# eCog002_Proto_SMD.net
KiCad netlist of a schematic drawn in EAGLE
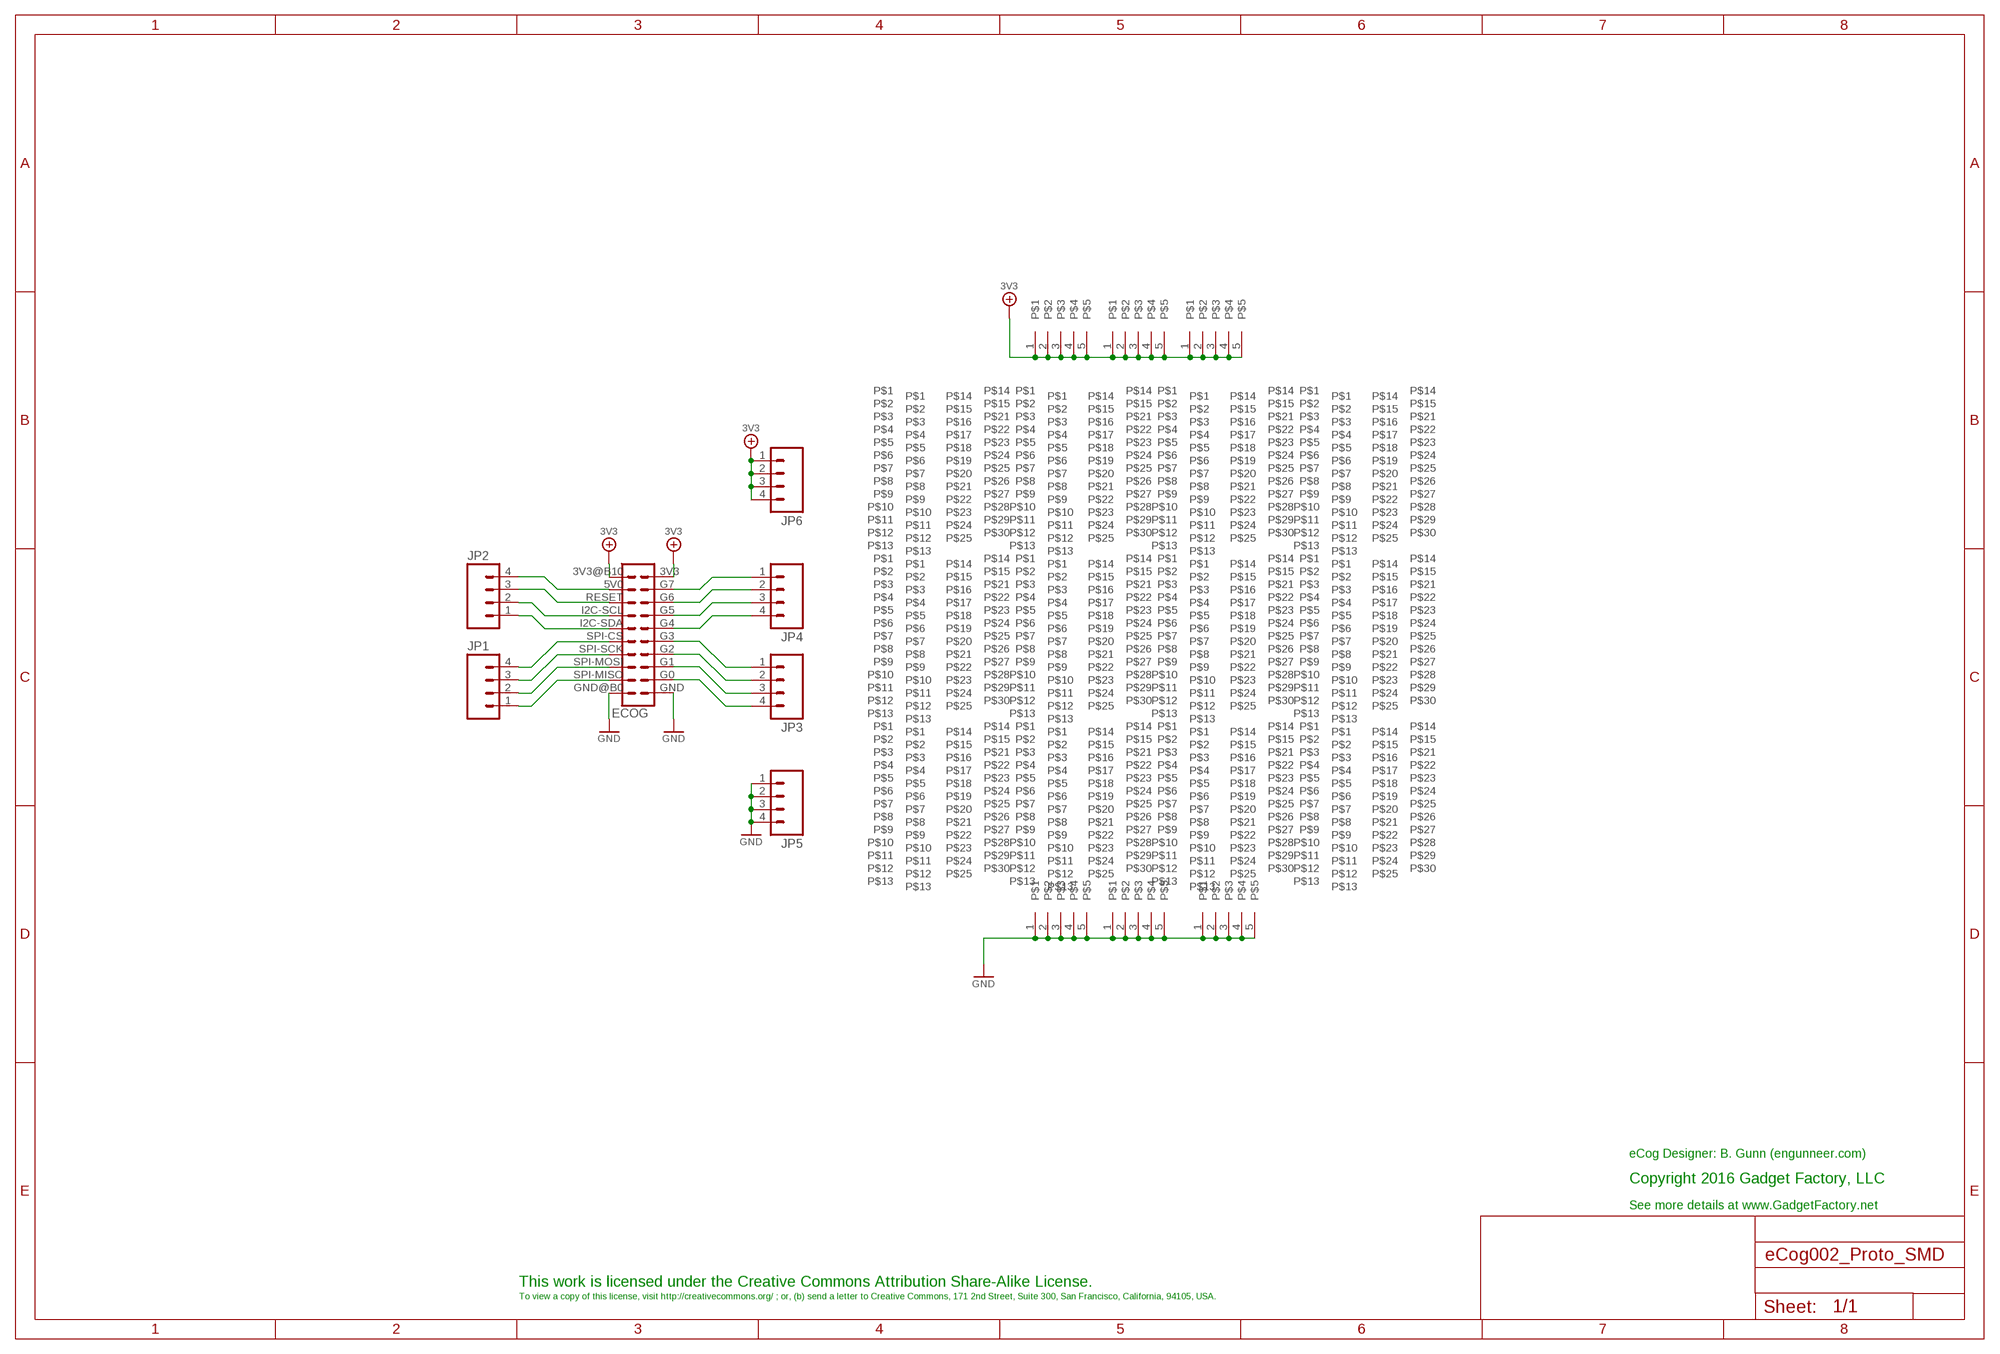
[diagram p0: schematic, sheet 1]

(export (version "E")
  (design (tool "Eeschema 10.0.6"))
  (components
    (comp (ref "ECOG")
      (value "ECOG_DUALTHROUGHHOLE")
      (footprint "eagle-import:ECOG_DUAL_TH")
      (libsource (lib "eagle-import") (part "ECOG_DUALTHROUGHHOLE"))
    )
    (comp (ref "JP1")
      (value "M041.27MM")
      (footprint "eagle-import:1X04-1.27MM")
      (libsource (lib "eagle-import") (part "M041.27MM"))
    )
    (comp (ref "JP2")
      (value "M041.27MM")
      (footprint "eagle-import:1X04-1.27MM")
      (libsource (lib "eagle-import") (part "M041.27MM"))
    )
    (comp (ref "JP3")
      (value "M041.27MM")
      (footprint "eagle-import:1X04-1.27MM")
      (libsource (lib "eagle-import") (part "M041.27MM"))
    )
    (comp (ref "JP4")
      (value "M041.27MM")
      (footprint "eagle-import:1X04-1.27MM")
      (libsource (lib "eagle-import") (part "M041.27MM"))
    )
    (comp (ref "JP5")
      (value "M041.27MM")
      (footprint "eagle-import:1X04-1.27MM")
      (libsource (lib "eagle-import") (part "M041.27MM"))
    )
    (comp (ref "JP6")
      (value "M041.27MM")
      (footprint "eagle-import:1X04-1.27MM")
      (libsource (lib "eagle-import") (part "M041.27MM"))
    )
    (comp (ref "U$2")
      (value "SMD_PROTO_2550X65")
      (footprint "eagle-import:SMD-5065")
      (libsource (lib "eagle-import") (part "SMD_PROTO_2550X65"))
    )
    (comp (ref "U$3")
      (value "SMD_PROTO_2550X65")
      (footprint "eagle-import:SMD-5065")
      (libsource (lib "eagle-import") (part "SMD_PROTO_2550X65"))
    )
    (comp (ref "U$4")
      (value "SMD_PROTO_2550X65")
      (footprint "eagle-import:SMD-5065")
      (libsource (lib "eagle-import") (part "SMD_PROTO_2550X65"))
    )
    (comp (ref "U$5")
      (value "SMD_PROTO_2550X65")
      (footprint "eagle-import:SMD-5065")
      (libsource (lib "eagle-import") (part "SMD_PROTO_2550X65"))
    )
    (comp (ref "U$6")
      (value "SMD_PROTO_2550X65")
      (footprint "eagle-import:SMD-5065")
      (libsource (lib "eagle-import") (part "SMD_PROTO_2550X65"))
    )
    (comp (ref "U$7")
      (value "SMD_PROTO_2550X65")
      (footprint "eagle-import:SMD-5065")
      (libsource (lib "eagle-import") (part "SMD_PROTO_2550X65"))
    )
    (comp (ref "U$8")
      (value "SMD_PROTO_2550X65")
      (footprint "eagle-import:SMD-5065")
      (libsource (lib "eagle-import") (part "SMD_PROTO_2550X65"))
    )
    (comp (ref "U$9")
      (value "SMD_PROTO_2550X65")
      (footprint "eagle-import:SMD-5065")
      (libsource (lib "eagle-import") (part "SMD_PROTO_2550X65"))
    )
    (comp (ref "U$11")
      (value "SMD_PROTO_2550X65")
      (footprint "eagle-import:SMD-5065")
      (libsource (lib "eagle-import") (part "SMD_PROTO_2550X65"))
    )
    (comp (ref "U$12")
      (value "SMD_PROTO_2550X65")
      (footprint "eagle-import:SMD-5065")
      (libsource (lib "eagle-import") (part "SMD_PROTO_2550X65"))
    )
    (comp (ref "U$13")
      (value "SMD_PROTO_2550X65")
      (footprint "eagle-import:SMD-5065")
      (libsource (lib "eagle-import") (part "SMD_PROTO_2550X65"))
    )
    (comp (ref "U$14")
      (value "SMD_PROTO_2550X65")
      (footprint "eagle-import:SMD-5065")
      (libsource (lib "eagle-import") (part "SMD_PROTO_2550X65"))
    )
    (comp (ref "U$15")
      (value "SMD_PROTO_55")
      (footprint "eagle-import:SMD-5065-5")
      (libsource (lib "eagle-import") (part "SMD_PROTO_55"))
    )
    (comp (ref "U$16")
      (value "SMD_PROTO_55")
      (footprint "eagle-import:SMD-5065-5")
      (libsource (lib "eagle-import") (part "SMD_PROTO_55"))
    )
    (comp (ref "U$17")
      (value "SMD_PROTO_55")
      (footprint "eagle-import:SMD-5065-5")
      (libsource (lib "eagle-import") (part "SMD_PROTO_55"))
    )
    (comp (ref "U$18")
      (value "SMD_PROTO_55")
      (footprint "eagle-import:SMD-5065-5")
      (libsource (lib "eagle-import") (part "SMD_PROTO_55"))
    )
    (comp (ref "U$19")
      (value "SMD_PROTO_55")
      (footprint "eagle-import:SMD-5065-5")
      (libsource (lib "eagle-import") (part "SMD_PROTO_55"))
    )
    (comp (ref "U$20")
      (value "SMD_PROTO_55")
      (footprint "eagle-import:SMD-5065-5")
      (libsource (lib "eagle-import") (part "SMD_PROTO_55"))
    )
  )
  (nets
    (net (code "1") (name "3V3") (class "Default")
      (node (ref "ECOG") (pin "3V3") (pinfunction "3V3_3V3") (pintype "passive"))
      (node (ref "ECOG") (pin "3V3@B10") (pinfunction "3V3_3V3@B10") (pintype "passive"))
      (node (ref "JP6") (pin "1") (pinfunction "1_1") (pintype "passive"))
      (node (ref "JP6") (pin "2") (pinfunction "2_2") (pintype "passive"))
      (node (ref "JP6") (pin "3") (pinfunction "3_3") (pintype "passive"))
      (node (ref "JP6") (pin "4") (pinfunction "4_4") (pintype "passive"))
      (node (ref "U$15") (pin "1") (pinfunction "P$1_1") (pintype "bidirectional"))
      (node (ref "U$15") (pin "2") (pinfunction "P$2_2") (pintype "bidirectional"))
      (node (ref "U$15") (pin "3") (pinfunction "P$3_3") (pintype "bidirectional"))
      (node (ref "U$15") (pin "4") (pinfunction "P$4_4") (pintype "bidirectional"))
      (node (ref "U$15") (pin "5") (pinfunction "P$5_5") (pintype "bidirectional"))
      (node (ref "U$16") (pin "1") (pinfunction "P$1_1") (pintype "bidirectional"))
      (node (ref "U$16") (pin "2") (pinfunction "P$2_2") (pintype "bidirectional"))
      (node (ref "U$16") (pin "3") (pinfunction "P$3_3") (pintype "bidirectional"))
      (node (ref "U$16") (pin "4") (pinfunction "P$4_4") (pintype "bidirectional"))
      (node (ref "U$16") (pin "5") (pinfunction "P$5_5") (pintype "bidirectional"))
      (node (ref "U$17") (pin "1") (pinfunction "P$1_1") (pintype "bidirectional"))
      (node (ref "U$17") (pin "2") (pinfunction "P$2_2") (pintype "bidirectional"))
      (node (ref "U$17") (pin "3") (pinfunction "P$3_3") (pintype "bidirectional"))
      (node (ref "U$17") (pin "4") (pinfunction "P$4_4") (pintype "bidirectional"))
      (node (ref "U$17") (pin "5") (pinfunction "P$5_5") (pintype "bidirectional"))
    )
    (net (code "2") (name "GND") (class "Default")
      (node (ref "ECOG") (pin "GND") (pinfunction "GND_GND") (pintype "passive"))
      (node (ref "ECOG") (pin "GND@B0") (pinfunction "GND_GND@B0") (pintype "passive"))
      (node (ref "JP5") (pin "1") (pinfunction "1_1") (pintype "passive"))
      (node (ref "JP5") (pin "2") (pinfunction "2_2") (pintype "passive"))
      (node (ref "JP5") (pin "3") (pinfunction "3_3") (pintype "passive"))
      (node (ref "JP5") (pin "4") (pinfunction "4_4") (pintype "passive"))
      (node (ref "U$18") (pin "1") (pinfunction "P$1_1") (pintype "bidirectional"))
      (node (ref "U$18") (pin "2") (pinfunction "P$2_2") (pintype "bidirectional"))
      (node (ref "U$18") (pin "3") (pinfunction "P$3_3") (pintype "bidirectional"))
      (node (ref "U$18") (pin "4") (pinfunction "P$4_4") (pintype "bidirectional"))
      (node (ref "U$18") (pin "5") (pinfunction "P$5_5") (pintype "bidirectional"))
      (node (ref "U$19") (pin "1") (pinfunction "P$1_1") (pintype "bidirectional"))
      (node (ref "U$19") (pin "2") (pinfunction "P$2_2") (pintype "bidirectional"))
      (node (ref "U$19") (pin "3") (pinfunction "P$3_3") (pintype "bidirectional"))
      (node (ref "U$19") (pin "4") (pinfunction "P$4_4") (pintype "bidirectional"))
      (node (ref "U$19") (pin "5") (pinfunction "P$5_5") (pintype "bidirectional"))
      (node (ref "U$20") (pin "1") (pinfunction "P$1_1") (pintype "bidirectional"))
      (node (ref "U$20") (pin "2") (pinfunction "P$2_2") (pintype "bidirectional"))
      (node (ref "U$20") (pin "3") (pinfunction "P$3_3") (pintype "bidirectional"))
      (node (ref "U$20") (pin "4") (pinfunction "P$4_4") (pintype "bidirectional"))
      (node (ref "U$20") (pin "5") (pinfunction "P$5_5") (pintype "bidirectional"))
    )
    (net (code "3") (name "Net-(ECOG-5V)") (class "Default")
      (node (ref "ECOG") (pin "5V0") (pinfunction "5V_5V0") (pintype "passive"))
      (node (ref "JP2") (pin "4") (pinfunction "4_4") (pintype "passive"))
    )
    (net (code "4") (name "Net-(ECOG-PadG0)") (class "Default")
      (node (ref "ECOG") (pin "G0") (pinfunction "G0_G0") (pintype "passive"))
      (node (ref "JP3") (pin "4") (pinfunction "4_4") (pintype "passive"))
    )
    (net (code "5") (name "Net-(ECOG-PadG1)") (class "Default")
      (node (ref "ECOG") (pin "G1") (pinfunction "G1_G1") (pintype "passive"))
      (node (ref "JP3") (pin "3") (pinfunction "3_3") (pintype "passive"))
    )
    (net (code "6") (name "Net-(ECOG-PadG2)") (class "Default")
      (node (ref "ECOG") (pin "G2") (pinfunction "G2_G2") (pintype "passive"))
      (node (ref "JP3") (pin "2") (pinfunction "2_2") (pintype "passive"))
    )
    (net (code "7") (name "Net-(ECOG-PadG3)") (class "Default")
      (node (ref "ECOG") (pin "G3") (pinfunction "G3_G3") (pintype "passive"))
      (node (ref "JP3") (pin "1") (pinfunction "1_1") (pintype "passive"))
    )
    (net (code "8") (name "Net-(ECOG-PadG4)") (class "Default")
      (node (ref "ECOG") (pin "G4") (pinfunction "G4_G4") (pintype "passive"))
      (node (ref "JP4") (pin "4") (pinfunction "4_4") (pintype "passive"))
    )
    (net (code "9") (name "Net-(ECOG-PadG5)") (class "Default")
      (node (ref "ECOG") (pin "G5") (pinfunction "G5_G5") (pintype "passive"))
      (node (ref "JP4") (pin "3") (pinfunction "3_3") (pintype "passive"))
    )
    (net (code "10") (name "Net-(ECOG-PadG6)") (class "Default")
      (node (ref "ECOG") (pin "G6") (pinfunction "G6_G6") (pintype "passive"))
      (node (ref "JP4") (pin "2") (pinfunction "2_2") (pintype "passive"))
    )
    (net (code "11") (name "Net-(ECOG-PadG7)") (class "Default")
      (node (ref "ECOG") (pin "G7") (pinfunction "G7_G7") (pintype "passive"))
      (node (ref "JP4") (pin "1") (pinfunction "1_1") (pintype "passive"))
    )
    (net (code "12") (name "Net-(ECOG-PadI2C-SCL)") (class "Default")
      (node (ref "ECOG") (pin "I2C-SCL") (pinfunction "I2C-SCL_I2C-SCL") (pintype "passive"))
      (node (ref "JP2") (pin "2") (pinfunction "2_2") (pintype "passive"))
    )
    (net (code "13") (name "Net-(ECOG-PadI2C-SDA)") (class "Default")
      (node (ref "ECOG") (pin "I2C-SDA") (pinfunction "I2C-SDA_I2C-SDA") (pintype "passive"))
      (node (ref "JP2") (pin "1") (pinfunction "1_1") (pintype "passive"))
    )
    (net (code "14") (name "Net-(ECOG-PadRESET)") (class "Default")
      (node (ref "ECOG") (pin "RESET") (pinfunction "RESET_RESET") (pintype "passive"))
      (node (ref "JP2") (pin "3") (pinfunction "3_3") (pintype "passive"))
    )
    (net (code "15") (name "Net-(ECOG-PadSPI-CS)") (class "Default")
      (node (ref "ECOG") (pin "SPI-CS") (pinfunction "SPI-CS_SPI-CS") (pintype "passive"))
      (node (ref "JP1") (pin "4") (pinfunction "4_4") (pintype "passive"))
    )
    (net (code "16") (name "Net-(ECOG-PadSPI-MISO)") (class "Default")
      (node (ref "ECOG") (pin "SPI-MISO") (pinfunction "SPI-MISO_SPI-MISO") (pintype "passive"))
      (node (ref "JP1") (pin "1") (pinfunction "1_1") (pintype "passive"))
    )
    (net (code "17") (name "Net-(ECOG-PadSPI-MOSI)") (class "Default")
      (node (ref "ECOG") (pin "SPI-MOSI") (pinfunction "SPI-MOSI_SPI-MOSI") (pintype "passive"))
      (node (ref "JP1") (pin "2") (pinfunction "2_2") (pintype "passive"))
    )
    (net (code "18") (name "Net-(ECOG-PadSPI-SCK)") (class "Default")
      (node (ref "ECOG") (pin "SPI-SCK") (pinfunction "SPI-SCK_SPI-SCK") (pintype "passive"))
      (node (ref "JP1") (pin "3") (pinfunction "3_3") (pintype "passive"))
    )
    (net (code "19") (name "unconnected-(U$2-P$16-PadP$21)") (class "Default")
      (node (ref "U$2") (pin "P$21") (pinfunction "P$16_P$21") (pintype "bidirectional"))
    )
    (net (code "20") (name "unconnected-(U$2-P$17-PadP$22)") (class "Default")
      (node (ref "U$2") (pin "P$22") (pinfunction "P$17_P$22") (pintype "bidirectional"))
    )
    (net (code "21") (name "unconnected-(U$2-P$18-PadP$23)") (class "Default")
      (node (ref "U$2") (pin "P$23") (pinfunction "P$18_P$23") (pintype "bidirectional"))
    )
    (net (code "22") (name "unconnected-(U$2-P$19-PadP$24)") (class "Default")
      (node (ref "U$2") (pin "P$24") (pinfunction "P$19_P$24") (pintype "bidirectional"))
    )
    (net (code "23") (name "unconnected-(U$2-P$20-PadP$25)") (class "Default")
      (node (ref "U$2") (pin "P$25") (pinfunction "P$20_P$25") (pintype "bidirectional"))
    )
    (net (code "24") (name "unconnected-(U$2-P$21-PadP$26)") (class "Default")
      (node (ref "U$2") (pin "P$26") (pinfunction "P$21_P$26") (pintype "bidirectional"))
    )
    (net (code "25") (name "unconnected-(U$2-P$22-PadP$27)") (class "Default")
      (node (ref "U$2") (pin "P$27") (pinfunction "P$22_P$27") (pintype "bidirectional"))
    )
    (net (code "26") (name "unconnected-(U$2-P$23-PadP$28)") (class "Default")
      (node (ref "U$2") (pin "P$28") (pinfunction "P$23_P$28") (pintype "bidirectional"))
    )
    (net (code "27") (name "unconnected-(U$2-P$24-PadP$29)") (class "Default")
      (node (ref "U$2") (pin "P$29") (pinfunction "P$24_P$29") (pintype "bidirectional"))
    )
    (net (code "28") (name "unconnected-(U$2-P$25-PadP$30)") (class "Default")
      (node (ref "U$2") (pin "P$30") (pinfunction "P$25_P$30") (pintype "bidirectional"))
    )
    (net (code "29") (name "unconnected-(U$2-PadP$1)") (class "Default")
      (node (ref "U$2") (pin "P$1") (pinfunction "P$1_P$1") (pintype "bidirectional"))
    )
    (net (code "30") (name "unconnected-(U$2-PadP$2)") (class "Default")
      (node (ref "U$2") (pin "P$2") (pinfunction "P$2_P$2") (pintype "bidirectional"))
    )
    (net (code "31") (name "unconnected-(U$2-PadP$3)") (class "Default")
      (node (ref "U$2") (pin "P$3") (pinfunction "P$3_P$3") (pintype "bidirectional"))
    )
    (net (code "32") (name "unconnected-(U$2-PadP$4)") (class "Default")
      (node (ref "U$2") (pin "P$4") (pinfunction "P$4_P$4") (pintype "bidirectional"))
    )
    (net (code "33") (name "unconnected-(U$2-PadP$5)") (class "Default")
      (node (ref "U$2") (pin "P$5") (pinfunction "P$5_P$5") (pintype "bidirectional"))
    )
    (net (code "34") (name "unconnected-(U$2-PadP$6)") (class "Default")
      (node (ref "U$2") (pin "P$6") (pinfunction "P$6_P$6") (pintype "bidirectional"))
    )
    (net (code "35") (name "unconnected-(U$2-PadP$7)") (class "Default")
      (node (ref "U$2") (pin "P$7") (pinfunction "P$7_P$7") (pintype "bidirectional"))
    )
    (net (code "36") (name "unconnected-(U$2-PadP$8)") (class "Default")
      (node (ref "U$2") (pin "P$8") (pinfunction "P$8_P$8") (pintype "bidirectional"))
    )
    (net (code "37") (name "unconnected-(U$2-PadP$9)") (class "Default")
      (node (ref "U$2") (pin "P$9") (pinfunction "P$9_P$9") (pintype "bidirectional"))
    )
    (net (code "38") (name "unconnected-(U$2-PadP$10)") (class "Default")
      (node (ref "U$2") (pin "P$10") (pinfunction "P$10_P$10") (pintype "bidirectional"))
    )
    (net (code "39") (name "unconnected-(U$2-PadP$11)") (class "Default")
      (node (ref "U$2") (pin "P$11") (pinfunction "P$11_P$11") (pintype "bidirectional"))
    )
    (net (code "40") (name "unconnected-(U$2-PadP$12)") (class "Default")
      (node (ref "U$2") (pin "P$12") (pinfunction "P$12_P$12") (pintype "bidirectional"))
    )
    (net (code "41") (name "unconnected-(U$2-PadP$13)") (class "Default")
      (node (ref "U$2") (pin "P$13") (pinfunction "P$13_P$13") (pintype "bidirectional"))
    )
    (net (code "42") (name "unconnected-(U$2-PadP$14)") (class "Default")
      (node (ref "U$2") (pin "P$14") (pinfunction "P$14_P$14") (pintype "bidirectional"))
    )
    (net (code "43") (name "unconnected-(U$2-PadP$15)") (class "Default")
      (node (ref "U$2") (pin "P$15") (pinfunction "P$15_P$15") (pintype "bidirectional"))
    )
    (net (code "44") (name "unconnected-(U$3-P$16-PadP$21)") (class "Default")
      (node (ref "U$3") (pin "P$21") (pinfunction "P$16_P$21") (pintype "bidirectional"))
    )
    (net (code "45") (name "unconnected-(U$3-P$17-PadP$22)") (class "Default")
      (node (ref "U$3") (pin "P$22") (pinfunction "P$17_P$22") (pintype "bidirectional"))
    )
    (net (code "46") (name "unconnected-(U$3-P$18-PadP$23)") (class "Default")
      (node (ref "U$3") (pin "P$23") (pinfunction "P$18_P$23") (pintype "bidirectional"))
    )
    (net (code "47") (name "unconnected-(U$3-P$19-PadP$24)") (class "Default")
      (node (ref "U$3") (pin "P$24") (pinfunction "P$19_P$24") (pintype "bidirectional"))
    )
    (net (code "48") (name "unconnected-(U$3-P$20-PadP$25)") (class "Default")
      (node (ref "U$3") (pin "P$25") (pinfunction "P$20_P$25") (pintype "bidirectional"))
    )
    (net (code "49") (name "unconnected-(U$3-P$21-PadP$26)") (class "Default")
      (node (ref "U$3") (pin "P$26") (pinfunction "P$21_P$26") (pintype "bidirectional"))
    )
    (net (code "50") (name "unconnected-(U$3-P$22-PadP$27)") (class "Default")
      (node (ref "U$3") (pin "P$27") (pinfunction "P$22_P$27") (pintype "bidirectional"))
    )
    (net (code "51") (name "unconnected-(U$3-P$23-PadP$28)") (class "Default")
      (node (ref "U$3") (pin "P$28") (pinfunction "P$23_P$28") (pintype "bidirectional"))
    )
    (net (code "52") (name "unconnected-(U$3-P$24-PadP$29)") (class "Default")
      (node (ref "U$3") (pin "P$29") (pinfunction "P$24_P$29") (pintype "bidirectional"))
    )
    (net (code "53") (name "unconnected-(U$3-P$25-PadP$30)") (class "Default")
      (node (ref "U$3") (pin "P$30") (pinfunction "P$25_P$30") (pintype "bidirectional"))
    )
    (net (code "54") (name "unconnected-(U$3-PadP$1)") (class "Default")
      (node (ref "U$3") (pin "P$1") (pinfunction "P$1_P$1") (pintype "bidirectional"))
    )
    (net (code "55") (name "unconnected-(U$3-PadP$2)") (class "Default")
      (node (ref "U$3") (pin "P$2") (pinfunction "P$2_P$2") (pintype "bidirectional"))
    )
    (net (code "56") (name "unconnected-(U$3-PadP$3)") (class "Default")
      (node (ref "U$3") (pin "P$3") (pinfunction "P$3_P$3") (pintype "bidirectional"))
    )
    (net (code "57") (name "unconnected-(U$3-PadP$4)") (class "Default")
      (node (ref "U$3") (pin "P$4") (pinfunction "P$4_P$4") (pintype "bidirectional"))
    )
    (net (code "58") (name "unconnected-(U$3-PadP$5)") (class "Default")
      (node (ref "U$3") (pin "P$5") (pinfunction "P$5_P$5") (pintype "bidirectional"))
    )
    (net (code "59") (name "unconnected-(U$3-PadP$6)") (class "Default")
      (node (ref "U$3") (pin "P$6") (pinfunction "P$6_P$6") (pintype "bidirectional"))
    )
    (net (code "60") (name "unconnected-(U$3-PadP$7)") (class "Default")
      (node (ref "U$3") (pin "P$7") (pinfunction "P$7_P$7") (pintype "bidirectional"))
    )
    (net (code "61") (name "unconnected-(U$3-PadP$8)") (class "Default")
      (node (ref "U$3") (pin "P$8") (pinfunction "P$8_P$8") (pintype "bidirectional"))
    )
    (net (code "62") (name "unconnected-(U$3-PadP$9)") (class "Default")
      (node (ref "U$3") (pin "P$9") (pinfunction "P$9_P$9") (pintype "bidirectional"))
    )
    (net (code "63") (name "unconnected-(U$3-PadP$10)") (class "Default")
      (node (ref "U$3") (pin "P$10") (pinfunction "P$10_P$10") (pintype "bidirectional"))
    )
    (net (code "64") (name "unconnected-(U$3-PadP$11)") (class "Default")
      (node (ref "U$3") (pin "P$11") (pinfunction "P$11_P$11") (pintype "bidirectional"))
    )
    (net (code "65") (name "unconnected-(U$3-PadP$12)") (class "Default")
      (node (ref "U$3") (pin "P$12") (pinfunction "P$12_P$12") (pintype "bidirectional"))
    )
    (net (code "66") (name "unconnected-(U$3-PadP$13)") (class "Default")
      (node (ref "U$3") (pin "P$13") (pinfunction "P$13_P$13") (pintype "bidirectional"))
    )
    (net (code "67") (name "unconnected-(U$3-PadP$14)") (class "Default")
      (node (ref "U$3") (pin "P$14") (pinfunction "P$14_P$14") (pintype "bidirectional"))
    )
    (net (code "68") (name "unconnected-(U$3-PadP$15)") (class "Default")
      (node (ref "U$3") (pin "P$15") (pinfunction "P$15_P$15") (pintype "bidirectional"))
    )
    (net (code "69") (name "unconnected-(U$4-P$16-PadP$21)") (class "Default")
      (node (ref "U$4") (pin "P$21") (pinfunction "P$16_P$21") (pintype "bidirectional"))
    )
    (net (code "70") (name "unconnected-(U$4-P$17-PadP$22)") (class "Default")
      (node (ref "U$4") (pin "P$22") (pinfunction "P$17_P$22") (pintype "bidirectional"))
    )
    (net (code "71") (name "unconnected-(U$4-P$18-PadP$23)") (class "Default")
      (node (ref "U$4") (pin "P$23") (pinfunction "P$18_P$23") (pintype "bidirectional"))
    )
    (net (code "72") (name "unconnected-(U$4-P$19-PadP$24)") (class "Default")
      (node (ref "U$4") (pin "P$24") (pinfunction "P$19_P$24") (pintype "bidirectional"))
    )
    (net (code "73") (name "unconnected-(U$4-P$20-PadP$25)") (class "Default")
      (node (ref "U$4") (pin "P$25") (pinfunction "P$20_P$25") (pintype "bidirectional"))
    )
    (net (code "74") (name "unconnected-(U$4-P$21-PadP$26)") (class "Default")
      (node (ref "U$4") (pin "P$26") (pinfunction "P$21_P$26") (pintype "bidirectional"))
    )
    (net (code "75") (name "unconnected-(U$4-P$22-PadP$27)") (class "Default")
      (node (ref "U$4") (pin "P$27") (pinfunction "P$22_P$27") (pintype "bidirectional"))
    )
    (net (code "76") (name "unconnected-(U$4-P$23-PadP$28)") (class "Default")
      (node (ref "U$4") (pin "P$28") (pinfunction "P$23_P$28") (pintype "bidirectional"))
    )
    (net (code "77") (name "unconnected-(U$4-P$24-PadP$29)") (class "Default")
      (node (ref "U$4") (pin "P$29") (pinfunction "P$24_P$29") (pintype "bidirectional"))
    )
    (net (code "78") (name "unconnected-(U$4-P$25-PadP$30)") (class "Default")
      (node (ref "U$4") (pin "P$30") (pinfunction "P$25_P$30") (pintype "bidirectional"))
    )
    (net (code "79") (name "unconnected-(U$4-PadP$1)") (class "Default")
      (node (ref "U$4") (pin "P$1") (pinfunction "P$1_P$1") (pintype "bidirectional"))
    )
    (net (code "80") (name "unconnected-(U$4-PadP$2)") (class "Default")
      (node (ref "U$4") (pin "P$2") (pinfunction "P$2_P$2") (pintype "bidirectional"))
    )
    (net (code "81") (name "unconnected-(U$4-PadP$3)") (class "Default")
      (node (ref "U$4") (pin "P$3") (pinfunction "P$3_P$3") (pintype "bidirectional"))
    )
    (net (code "82") (name "unconnected-(U$4-PadP$4)") (class "Default")
      (node (ref "U$4") (pin "P$4") (pinfunction "P$4_P$4") (pintype "bidirectional"))
    )
    (net (code "83") (name "unconnected-(U$4-PadP$5)") (class "Default")
      (node (ref "U$4") (pin "P$5") (pinfunction "P$5_P$5") (pintype "bidirectional"))
    )
    (net (code "84") (name "unconnected-(U$4-PadP$6)") (class "Default")
      (node (ref "U$4") (pin "P$6") (pinfunction "P$6_P$6") (pintype "bidirectional"))
    )
    (net (code "85") (name "unconnected-(U$4-PadP$7)") (class "Default")
      (node (ref "U$4") (pin "P$7") (pinfunction "P$7_P$7") (pintype "bidirectional"))
    )
    (net (code "86") (name "unconnected-(U$4-PadP$8)") (class "Default")
      (node (ref "U$4") (pin "P$8") (pinfunction "P$8_P$8") (pintype "bidirectional"))
    )
    (net (code "87") (name "unconnected-(U$4-PadP$9)") (class "Default")
      (node (ref "U$4") (pin "P$9") (pinfunction "P$9_P$9") (pintype "bidirectional"))
    )
    (net (code "88") (name "unconnected-(U$4-PadP$10)") (class "Default")
      (node (ref "U$4") (pin "P$10") (pinfunction "P$10_P$10") (pintype "bidirectional"))
    )
    (net (code "89") (name "unconnected-(U$4-PadP$11)") (class "Default")
      (node (ref "U$4") (pin "P$11") (pinfunction "P$11_P$11") (pintype "bidirectional"))
    )
    (net (code "90") (name "unconnected-(U$4-PadP$12)") (class "Default")
      (node (ref "U$4") (pin "P$12") (pinfunction "P$12_P$12") (pintype "bidirectional"))
    )
    (net (code "91") (name "unconnected-(U$4-PadP$13)") (class "Default")
      (node (ref "U$4") (pin "P$13") (pinfunction "P$13_P$13") (pintype "bidirectional"))
    )
    (net (code "92") (name "unconnected-(U$4-PadP$14)") (class "Default")
      (node (ref "U$4") (pin "P$14") (pinfunction "P$14_P$14") (pintype "bidirectional"))
    )
    (net (code "93") (name "unconnected-(U$4-PadP$15)") (class "Default")
      (node (ref "U$4") (pin "P$15") (pinfunction "P$15_P$15") (pintype "bidirectional"))
    )
    (net (code "94") (name "unconnected-(U$5-P$16-PadP$21)") (class "Default")
      (node (ref "U$5") (pin "P$21") (pinfunction "P$16_P$21") (pintype "bidirectional"))
    )
    (net (code "95") (name "unconnected-(U$5-P$17-PadP$22)") (class "Default")
      (node (ref "U$5") (pin "P$22") (pinfunction "P$17_P$22") (pintype "bidirectional"))
    )
    (net (code "96") (name "unconnected-(U$5-P$18-PadP$23)") (class "Default")
      (node (ref "U$5") (pin "P$23") (pinfunction "P$18_P$23") (pintype "bidirectional"))
    )
    (net (code "97") (name "unconnected-(U$5-P$19-PadP$24)") (class "Default")
      (node (ref "U$5") (pin "P$24") (pinfunction "P$19_P$24") (pintype "bidirectional"))
    )
    (net (code "98") (name "unconnected-(U$5-P$20-PadP$25)") (class "Default")
      (node (ref "U$5") (pin "P$25") (pinfunction "P$20_P$25") (pintype "bidirectional"))
    )
    (net (code "99") (name "unconnected-(U$5-P$21-PadP$26)") (class "Default")
      (node (ref "U$5") (pin "P$26") (pinfunction "P$21_P$26") (pintype "bidirectional"))
    )
    (net (code "100") (name "unconnected-(U$5-P$22-PadP$27)") (class "Default")
      (node (ref "U$5") (pin "P$27") (pinfunction "P$22_P$27") (pintype "bidirectional"))
    )
    (net (code "101") (name "unconnected-(U$5-P$23-PadP$28)") (class "Default")
      (node (ref "U$5") (pin "P$28") (pinfunction "P$23_P$28") (pintype "bidirectional"))
    )
    (net (code "102") (name "unconnected-(U$5-P$24-PadP$29)") (class "Default")
      (node (ref "U$5") (pin "P$29") (pinfunction "P$24_P$29") (pintype "bidirectional"))
    )
    (net (code "103") (name "unconnected-(U$5-P$25-PadP$30)") (class "Default")
      (node (ref "U$5") (pin "P$30") (pinfunction "P$25_P$30") (pintype "bidirectional"))
    )
    (net (code "104") (name "unconnected-(U$5-PadP$1)") (class "Default")
      (node (ref "U$5") (pin "P$1") (pinfunction "P$1_P$1") (pintype "bidirectional"))
    )
    (net (code "105") (name "unconnected-(U$5-PadP$2)") (class "Default")
      (node (ref "U$5") (pin "P$2") (pinfunction "P$2_P$2") (pintype "bidirectional"))
    )
    (net (code "106") (name "unconnected-(U$5-PadP$3)") (class "Default")
      (node (ref "U$5") (pin "P$3") (pinfunction "P$3_P$3") (pintype "bidirectional"))
    )
    (net (code "107") (name "unconnected-(U$5-PadP$4)") (class "Default")
      (node (ref "U$5") (pin "P$4") (pinfunction "P$4_P$4") (pintype "bidirectional"))
    )
    (net (code "108") (name "unconnected-(U$5-PadP$5)") (class "Default")
      (node (ref "U$5") (pin "P$5") (pinfunction "P$5_P$5") (pintype "bidirectional"))
    )
    (net (code "109") (name "unconnected-(U$5-PadP$6)") (class "Default")
      (node (ref "U$5") (pin "P$6") (pinfunction "P$6_P$6") (pintype "bidirectional"))
    )
    (net (code "110") (name "unconnected-(U$5-PadP$7)") (class "Default")
      (node (ref "U$5") (pin "P$7") (pinfunction "P$7_P$7") (pintype "bidirectional"))
    )
    (net (code "111") (name "unconnected-(U$5-PadP$8)") (class "Default")
      (node (ref "U$5") (pin "P$8") (pinfunction "P$8_P$8") (pintype "bidirectional"))
    )
    (net (code "112") (name "unconnected-(U$5-PadP$9)") (class "Default")
      (node (ref "U$5") (pin "P$9") (pinfunction "P$9_P$9") (pintype "bidirectional"))
    )
    (net (code "113") (name "unconnected-(U$5-PadP$10)") (class "Default")
      (node (ref "U$5") (pin "P$10") (pinfunction "P$10_P$10") (pintype "bidirectional"))
    )
    (net (code "114") (name "unconnected-(U$5-PadP$11)") (class "Default")
      (node (ref "U$5") (pin "P$11") (pinfunction "P$11_P$11") (pintype "bidirectional"))
    )
    (net (code "115") (name "unconnected-(U$5-PadP$12)") (class "Default")
      (node (ref "U$5") (pin "P$12") (pinfunction "P$12_P$12") (pintype "bidirectional"))
    )
    (net (code "116") (name "unconnected-(U$5-PadP$13)") (class "Default")
      (node (ref "U$5") (pin "P$13") (pinfunction "P$13_P$13") (pintype "bidirectional"))
    )
    (net (code "117") (name "unconnected-(U$5-PadP$14)") (class "Default")
      (node (ref "U$5") (pin "P$14") (pinfunction "P$14_P$14") (pintype "bidirectional"))
    )
    (net (code "118") (name "unconnected-(U$5-PadP$15)") (class "Default")
      (node (ref "U$5") (pin "P$15") (pinfunction "P$15_P$15") (pintype "bidirectional"))
    )
    (net (code "119") (name "unconnected-(U$6-P$16-PadP$21)") (class "Default")
      (node (ref "U$6") (pin "P$21") (pinfunction "P$16_P$21") (pintype "bidirectional"))
    )
    (net (code "120") (name "unconnected-(U$6-P$17-PadP$22)") (class "Default")
      (node (ref "U$6") (pin "P$22") (pinfunction "P$17_P$22") (pintype "bidirectional"))
    )
    (net (code "121") (name "unconnected-(U$6-P$18-PadP$23)") (class "Default")
      (node (ref "U$6") (pin "P$23") (pinfunction "P$18_P$23") (pintype "bidirectional"))
    )
    (net (code "122") (name "unconnected-(U$6-P$19-PadP$24)") (class "Default")
      (node (ref "U$6") (pin "P$24") (pinfunction "P$19_P$24") (pintype "bidirectional"))
    )
    (net (code "123") (name "unconnected-(U$6-P$20-PadP$25)") (class "Default")
      (node (ref "U$6") (pin "P$25") (pinfunction "P$20_P$25") (pintype "bidirectional"))
    )
    (net (code "124") (name "unconnected-(U$6-P$21-PadP$26)") (class "Default")
      (node (ref "U$6") (pin "P$26") (pinfunction "P$21_P$26") (pintype "bidirectional"))
    )
    (net (code "125") (name "unconnected-(U$6-P$22-PadP$27)") (class "Default")
      (node (ref "U$6") (pin "P$27") (pinfunction "P$22_P$27") (pintype "bidirectional"))
    )
    (net (code "126") (name "unconnected-(U$6-P$23-PadP$28)") (class "Default")
      (node (ref "U$6") (pin "P$28") (pinfunction "P$23_P$28") (pintype "bidirectional"))
    )
    (net (code "127") (name "unconnected-(U$6-P$24-PadP$29)") (class "Default")
      (node (ref "U$6") (pin "P$29") (pinfunction "P$24_P$29") (pintype "bidirectional"))
    )
    (net (code "128") (name "unconnected-(U$6-P$25-PadP$30)") (class "Default")
      (node (ref "U$6") (pin "P$30") (pinfunction "P$25_P$30") (pintype "bidirectional"))
    )
    (net (code "129") (name "unconnected-(U$6-PadP$1)") (class "Default")
      (node (ref "U$6") (pin "P$1") (pinfunction "P$1_P$1") (pintype "bidirectional"))
    )
    (net (code "130") (name "unconnected-(U$6-PadP$2)") (class "Default")
      (node (ref "U$6") (pin "P$2") (pinfunction "P$2_P$2") (pintype "bidirectional"))
    )
    (net (code "131") (name "unconnected-(U$6-PadP$3)") (class "Default")
      (node (ref "U$6") (pin "P$3") (pinfunction "P$3_P$3") (pintype "bidirectional"))
    )
    (net (code "132") (name "unconnected-(U$6-PadP$4)") (class "Default")
      (node (ref "U$6") (pin "P$4") (pinfunction "P$4_P$4") (pintype "bidirectional"))
    )
    (net (code "133") (name "unconnected-(U$6-PadP$5)") (class "Default")
      (node (ref "U$6") (pin "P$5") (pinfunction "P$5_P$5") (pintype "bidirectional"))
    )
    (net (code "134") (name "unconnected-(U$6-PadP$6)") (class "Default")
      (node (ref "U$6") (pin "P$6") (pinfunction "P$6_P$6") (pintype "bidirectional"))
    )
    (net (code "135") (name "unconnected-(U$6-PadP$7)") (class "Default")
      (node (ref "U$6") (pin "P$7") (pinfunction "P$7_P$7") (pintype "bidirectional"))
    )
    (net (code "136") (name "unconnected-(U$6-PadP$8)") (class "Default")
      (node (ref "U$6") (pin "P$8") (pinfunction "P$8_P$8") (pintype "bidirectional"))
    )
    (net (code "137") (name "unconnected-(U$6-PadP$9)") (class "Default")
      (node (ref "U$6") (pin "P$9") (pinfunction "P$9_P$9") (pintype "bidirectional"))
    )
    (net (code "138") (name "unconnected-(U$6-PadP$10)") (class "Default")
      (node (ref "U$6") (pin "P$10") (pinfunction "P$10_P$10") (pintype "bidirectional"))
    )
    (net (code "139") (name "unconnected-(U$6-PadP$11)") (class "Default")
      (node (ref "U$6") (pin "P$11") (pinfunction "P$11_P$11") (pintype "bidirectional"))
    )
    (net (code "140") (name "unconnected-(U$6-PadP$12)") (class "Default")
      (node (ref "U$6") (pin "P$12") (pinfunction "P$12_P$12") (pintype "bidirectional"))
    )
    (net (code "141") (name "unconnected-(U$6-PadP$13)") (class "Default")
      (node (ref "U$6") (pin "P$13") (pinfunction "P$13_P$13") (pintype "bidirectional"))
    )
    (net (code "142") (name "unconnected-(U$6-PadP$14)") (class "Default")
      (node (ref "U$6") (pin "P$14") (pinfunction "P$14_P$14") (pintype "bidirectional"))
    )
    (net (code "143") (name "unconnected-(U$6-PadP$15)") (class "Default")
      (node (ref "U$6") (pin "P$15") (pinfunction "P$15_P$15") (pintype "bidirectional"))
    )
    (net (code "144") (name "unconnected-(U$7-P$16-PadP$21)") (class "Default")
      (node (ref "U$7") (pin "P$21") (pinfunction "P$16_P$21") (pintype "bidirectional"))
    )
    (net (code "145") (name "unconnected-(U$7-P$17-PadP$22)") (class "Default")
      (node (ref "U$7") (pin "P$22") (pinfunction "P$17_P$22") (pintype "bidirectional"))
    )
    (net (code "146") (name "unconnected-(U$7-P$18-PadP$23)") (class "Default")
      (node (ref "U$7") (pin "P$23") (pinfunction "P$18_P$23") (pintype "bidirectional"))
    )
    (net (code "147") (name "unconnected-(U$7-P$19-PadP$24)") (class "Default")
      (node (ref "U$7") (pin "P$24") (pinfunction "P$19_P$24") (pintype "bidirectional"))
    )
    (net (code "148") (name "unconnected-(U$7-P$20-PadP$25)") (class "Default")
      (node (ref "U$7") (pin "P$25") (pinfunction "P$20_P$25") (pintype "bidirectional"))
    )
    (net (code "149") (name "unconnected-(U$7-P$21-PadP$26)") (class "Default")
      (node (ref "U$7") (pin "P$26") (pinfunction "P$21_P$26") (pintype "bidirectional"))
    )
    (net (code "150") (name "unconnected-(U$7-P$22-PadP$27)") (class "Default")
      (node (ref "U$7") (pin "P$27") (pinfunction "P$22_P$27") (pintype "bidirectional"))
    )
    (net (code "151") (name "unconnected-(U$7-P$23-PadP$28)") (class "Default")
      (node (ref "U$7") (pin "P$28") (pinfunction "P$23_P$28") (pintype "bidirectional"))
    )
    (net (code "152") (name "unconnected-(U$7-P$24-PadP$29)") (class "Default")
      (node (ref "U$7") (pin "P$29") (pinfunction "P$24_P$29") (pintype "bidirectional"))
    )
    (net (code "153") (name "unconnected-(U$7-P$25-PadP$30)") (class "Default")
      (node (ref "U$7") (pin "P$30") (pinfunction "P$25_P$30") (pintype "bidirectional"))
    )
    (net (code "154") (name "unconnected-(U$7-PadP$1)") (class "Default")
      (node (ref "U$7") (pin "P$1") (pinfunction "P$1_P$1") (pintype "bidirectional"))
    )
    (net (code "155") (name "unconnected-(U$7-PadP$2)") (class "Default")
      (node (ref "U$7") (pin "P$2") (pinfunction "P$2_P$2") (pintype "bidirectional"))
    )
    (net (code "156") (name "unconnected-(U$7-PadP$3)") (class "Default")
      (node (ref "U$7") (pin "P$3") (pinfunction "P$3_P$3") (pintype "bidirectional"))
    )
    (net (code "157") (name "unconnected-(U$7-PadP$4)") (class "Default")
      (node (ref "U$7") (pin "P$4") (pinfunction "P$4_P$4") (pintype "bidirectional"))
    )
    (net (code "158") (name "unconnected-(U$7-PadP$5)") (class "Default")
      (node (ref "U$7") (pin "P$5") (pinfunction "P$5_P$5") (pintype "bidirectional"))
    )
    (net (code "159") (name "unconnected-(U$7-PadP$6)") (class "Default")
      (node (ref "U$7") (pin "P$6") (pinfunction "P$6_P$6") (pintype "bidirectional"))
    )
    (net (code "160") (name "unconnected-(U$7-PadP$7)") (class "Default")
      (node (ref "U$7") (pin "P$7") (pinfunction "P$7_P$7") (pintype "bidirectional"))
    )
    (net (code "161") (name "unconnected-(U$7-PadP$8)") (class "Default")
      (node (ref "U$7") (pin "P$8") (pinfunction "P$8_P$8") (pintype "bidirectional"))
    )
    (net (code "162") (name "unconnected-(U$7-PadP$9)") (class "Default")
      (node (ref "U$7") (pin "P$9") (pinfunction "P$9_P$9") (pintype "bidirectional"))
    )
    (net (code "163") (name "unconnected-(U$7-PadP$10)") (class "Default")
      (node (ref "U$7") (pin "P$10") (pinfunction "P$10_P$10") (pintype "bidirectional"))
    )
    (net (code "164") (name "unconnected-(U$7-PadP$11)") (class "Default")
      (node (ref "U$7") (pin "P$11") (pinfunction "P$11_P$11") (pintype "bidirectional"))
    )
    (net (code "165") (name "unconnected-(U$7-PadP$12)") (class "Default")
      (node (ref "U$7") (pin "P$12") (pinfunction "P$12_P$12") (pintype "bidirectional"))
    )
    (net (code "166") (name "unconnected-(U$7-PadP$13)") (class "Default")
      (node (ref "U$7") (pin "P$13") (pinfunction "P$13_P$13") (pintype "bidirectional"))
    )
    (net (code "167") (name "unconnected-(U$7-PadP$14)") (class "Default")
      (node (ref "U$7") (pin "P$14") (pinfunction "P$14_P$14") (pintype "bidirectional"))
    )
    (net (code "168") (name "unconnected-(U$7-PadP$15)") (class "Default")
      (node (ref "U$7") (pin "P$15") (pinfunction "P$15_P$15") (pintype "bidirectional"))
    )
    (net (code "169") (name "unconnected-(U$8-P$16-PadP$21)") (class "Default")
      (node (ref "U$8") (pin "P$21") (pinfunction "P$16_P$21") (pintype "bidirectional"))
    )
    (net (code "170") (name "unconnected-(U$8-P$17-PadP$22)") (class "Default")
      (node (ref "U$8") (pin "P$22") (pinfunction "P$17_P$22") (pintype "bidirectional"))
    )
    (net (code "171") (name "unconnected-(U$8-P$18-PadP$23)") (class "Default")
      (node (ref "U$8") (pin "P$23") (pinfunction "P$18_P$23") (pintype "bidirectional"))
    )
    (net (code "172") (name "unconnected-(U$8-P$19-PadP$24)") (class "Default")
      (node (ref "U$8") (pin "P$24") (pinfunction "P$19_P$24") (pintype "bidirectional"))
    )
    (net (code "173") (name "unconnected-(U$8-P$20-PadP$25)") (class "Default")
      (node (ref "U$8") (pin "P$25") (pinfunction "P$20_P$25") (pintype "bidirectional"))
    )
    (net (code "174") (name "unconnected-(U$8-P$21-PadP$26)") (class "Default")
      (node (ref "U$8") (pin "P$26") (pinfunction "P$21_P$26") (pintype "bidirectional"))
    )
    (net (code "175") (name "unconnected-(U$8-P$22-PadP$27)") (class "Default")
      (node (ref "U$8") (pin "P$27") (pinfunction "P$22_P$27") (pintype "bidirectional"))
    )
    (net (code "176") (name "unconnected-(U$8-P$23-PadP$28)") (class "Default")
      (node (ref "U$8") (pin "P$28") (pinfunction "P$23_P$28") (pintype "bidirectional"))
    )
    (net (code "177") (name "unconnected-(U$8-P$24-PadP$29)") (class "Default")
      (node (ref "U$8") (pin "P$29") (pinfunction "P$24_P$29") (pintype "bidirectional"))
    )
    (net (code "178") (name "unconnected-(U$8-P$25-PadP$30)") (class "Default")
      (node (ref "U$8") (pin "P$30") (pinfunction "P$25_P$30") (pintype "bidirectional"))
    )
    (net (code "179") (name "unconnected-(U$8-PadP$1)") (class "Default")
      (node (ref "U$8") (pin "P$1") (pinfunction "P$1_P$1") (pintype "bidirectional"))
    )
    (net (code "180") (name "unconnected-(U$8-PadP$2)") (class "Default")
      (node (ref "U$8") (pin "P$2") (pinfunction "P$2_P$2") (pintype "bidirectional"))
    )
    (net (code "181") (name "unconnected-(U$8-PadP$3)") (class "Default")
      (node (ref "U$8") (pin "P$3") (pinfunction "P$3_P$3") (pintype "bidirectional"))
    )
    (net (code "182") (name "unconnected-(U$8-PadP$4)") (class "Default")
      (node (ref "U$8") (pin "P$4") (pinfunction "P$4_P$4") (pintype "bidirectional"))
    )
    (net (code "183") (name "unconnected-(U$8-PadP$5)") (class "Default")
      (node (ref "U$8") (pin "P$5") (pinfunction "P$5_P$5") (pintype "bidirectional"))
    )
    (net (code "184") (name "unconnected-(U$8-PadP$6)") (class "Default")
      (node (ref "U$8") (pin "P$6") (pinfunction "P$6_P$6") (pintype "bidirectional"))
    )
    (net (code "185") (name "unconnected-(U$8-PadP$7)") (class "Default")
      (node (ref "U$8") (pin "P$7") (pinfunction "P$7_P$7") (pintype "bidirectional"))
    )
    (net (code "186") (name "unconnected-(U$8-PadP$8)") (class "Default")
      (node (ref "U$8") (pin "P$8") (pinfunction "P$8_P$8") (pintype "bidirectional"))
    )
    (net (code "187") (name "unconnected-(U$8-PadP$9)") (class "Default")
      (node (ref "U$8") (pin "P$9") (pinfunction "P$9_P$9") (pintype "bidirectional"))
    )
    (net (code "188") (name "unconnected-(U$8-PadP$10)") (class "Default")
      (node (ref "U$8") (pin "P$10") (pinfunction "P$10_P$10") (pintype "bidirectional"))
    )
    (net (code "189") (name "unconnected-(U$8-PadP$11)") (class "Default")
      (node (ref "U$8") (pin "P$11") (pinfunction "P$11_P$11") (pintype "bidirectional"))
    )
    (net (code "190") (name "unconnected-(U$8-PadP$12)") (class "Default")
      (node (ref "U$8") (pin "P$12") (pinfunction "P$12_P$12") (pintype "bidirectional"))
    )
    (net (code "191") (name "unconnected-(U$8-PadP$13)") (class "Default")
      (node (ref "U$8") (pin "P$13") (pinfunction "P$13_P$13") (pintype "bidirectional"))
    )
    (net (code "192") (name "unconnected-(U$8-PadP$14)") (class "Default")
      (node (ref "U$8") (pin "P$14") (pinfunction "P$14_P$14") (pintype "bidirectional"))
    )
    (net (code "193") (name "unconnected-(U$8-PadP$15)") (class "Default")
      (node (ref "U$8") (pin "P$15") (pinfunction "P$15_P$15") (pintype "bidirectional"))
    )
    (net (code "194") (name "unconnected-(U$9-P$16-PadP$21)") (class "Default")
      (node (ref "U$9") (pin "P$21") (pinfunction "P$16_P$21") (pintype "bidirectional"))
    )
    (net (code "195") (name "unconnected-(U$9-P$17-PadP$22)") (class "Default")
      (node (ref "U$9") (pin "P$22") (pinfunction "P$17_P$22") (pintype "bidirectional"))
    )
    (net (code "196") (name "unconnected-(U$9-P$18-PadP$23)") (class "Default")
      (node (ref "U$9") (pin "P$23") (pinfunction "P$18_P$23") (pintype "bidirectional"))
    )
    (net (code "197") (name "unconnected-(U$9-P$19-PadP$24)") (class "Default")
      (node (ref "U$9") (pin "P$24") (pinfunction "P$19_P$24") (pintype "bidirectional"))
    )
    (net (code "198") (name "unconnected-(U$9-P$20-PadP$25)") (class "Default")
      (node (ref "U$9") (pin "P$25") (pinfunction "P$20_P$25") (pintype "bidirectional"))
    )
    (net (code "199") (name "unconnected-(U$9-P$21-PadP$26)") (class "Default")
      (node (ref "U$9") (pin "P$26") (pinfunction "P$21_P$26") (pintype "bidirectional"))
    )
    (net (code "200") (name "unconnected-(U$9-P$22-PadP$27)") (class "Default")
      (node (ref "U$9") (pin "P$27") (pinfunction "P$22_P$27") (pintype "bidirectional"))
    )
    (net (code "201") (name "unconnected-(U$9-P$23-PadP$28)") (class "Default")
      (node (ref "U$9") (pin "P$28") (pinfunction "P$23_P$28") (pintype "bidirectional"))
    )
    (net (code "202") (name "unconnected-(U$9-P$24-PadP$29)") (class "Default")
      (node (ref "U$9") (pin "P$29") (pinfunction "P$24_P$29") (pintype "bidirectional"))
    )
    (net (code "203") (name "unconnected-(U$9-P$25-PadP$30)") (class "Default")
      (node (ref "U$9") (pin "P$30") (pinfunction "P$25_P$30") (pintype "bidirectional"))
    )
    (net (code "204") (name "unconnected-(U$9-PadP$1)") (class "Default")
      (node (ref "U$9") (pin "P$1") (pinfunction "P$1_P$1") (pintype "bidirectional"))
    )
    (net (code "205") (name "unconnected-(U$9-PadP$2)") (class "Default")
      (node (ref "U$9") (pin "P$2") (pinfunction "P$2_P$2") (pintype "bidirectional"))
    )
    (net (code "206") (name "unconnected-(U$9-PadP$3)") (class "Default")
      (node (ref "U$9") (pin "P$3") (pinfunction "P$3_P$3") (pintype "bidirectional"))
    )
    (net (code "207") (name "unconnected-(U$9-PadP$4)") (class "Default")
      (node (ref "U$9") (pin "P$4") (pinfunction "P$4_P$4") (pintype "bidirectional"))
    )
    (net (code "208") (name "unconnected-(U$9-PadP$5)") (class "Default")
      (node (ref "U$9") (pin "P$5") (pinfunction "P$5_P$5") (pintype "bidirectional"))
    )
    (net (code "209") (name "unconnected-(U$9-PadP$6)") (class "Default")
      (node (ref "U$9") (pin "P$6") (pinfunction "P$6_P$6") (pintype "bidirectional"))
    )
    (net (code "210") (name "unconnected-(U$9-PadP$7)") (class "Default")
      (node (ref "U$9") (pin "P$7") (pinfunction "P$7_P$7") (pintype "bidirectional"))
    )
    (net (code "211") (name "unconnected-(U$9-PadP$8)") (class "Default")
      (node (ref "U$9") (pin "P$8") (pinfunction "P$8_P$8") (pintype "bidirectional"))
    )
    (net (code "212") (name "unconnected-(U$9-PadP$9)") (class "Default")
      (node (ref "U$9") (pin "P$9") (pinfunction "P$9_P$9") (pintype "bidirectional"))
    )
    (net (code "213") (name "unconnected-(U$9-PadP$10)") (class "Default")
      (node (ref "U$9") (pin "P$10") (pinfunction "P$10_P$10") (pintype "bidirectional"))
    )
    (net (code "214") (name "unconnected-(U$9-PadP$11)") (class "Default")
      (node (ref "U$9") (pin "P$11") (pinfunction "P$11_P$11") (pintype "bidirectional"))
    )
    (net (code "215") (name "unconnected-(U$9-PadP$12)") (class "Default")
      (node (ref "U$9") (pin "P$12") (pinfunction "P$12_P$12") (pintype "bidirectional"))
    )
    (net (code "216") (name "unconnected-(U$9-PadP$13)") (class "Default")
      (node (ref "U$9") (pin "P$13") (pinfunction "P$13_P$13") (pintype "bidirectional"))
    )
    (net (code "217") (name "unconnected-(U$9-PadP$14)") (class "Default")
      (node (ref "U$9") (pin "P$14") (pinfunction "P$14_P$14") (pintype "bidirectional"))
    )
    (net (code "218") (name "unconnected-(U$9-PadP$15)") (class "Default")
      (node (ref "U$9") (pin "P$15") (pinfunction "P$15_P$15") (pintype "bidirectional"))
    )
    (net (code "219") (name "unconnected-(U$11-P$16-PadP$21)") (class "Default")
      (node (ref "U$11") (pin "P$21") (pinfunction "P$16_P$21") (pintype "bidirectional"))
    )
    (net (code "220") (name "unconnected-(U$11-P$17-PadP$22)") (class "Default")
      (node (ref "U$11") (pin "P$22") (pinfunction "P$17_P$22") (pintype "bidirectional"))
    )
    (net (code "221") (name "unconnected-(U$11-P$18-PadP$23)") (class "Default")
      (node (ref "U$11") (pin "P$23") (pinfunction "P$18_P$23") (pintype "bidirectional"))
    )
    (net (code "222") (name "unconnected-(U$11-P$19-PadP$24)") (class "Default")
      (node (ref "U$11") (pin "P$24") (pinfunction "P$19_P$24") (pintype "bidirectional"))
    )
    (net (code "223") (name "unconnected-(U$11-P$20-PadP$25)") (class "Default")
      (node (ref "U$11") (pin "P$25") (pinfunction "P$20_P$25") (pintype "bidirectional"))
    )
    (net (code "224") (name "unconnected-(U$11-P$21-PadP$26)") (class "Default")
      (node (ref "U$11") (pin "P$26") (pinfunction "P$21_P$26") (pintype "bidirectional"))
    )
    (net (code "225") (name "unconnected-(U$11-P$22-PadP$27)") (class "Default")
      (node (ref "U$11") (pin "P$27") (pinfunction "P$22_P$27") (pintype "bidirectional"))
    )
    (net (code "226") (name "unconnected-(U$11-P$23-PadP$28)") (class "Default")
      (node (ref "U$11") (pin "P$28") (pinfunction "P$23_P$28") (pintype "bidirectional"))
    )
    (net (code "227") (name "unconnected-(U$11-P$24-PadP$29)") (class "Default")
      (node (ref "U$11") (pin "P$29") (pinfunction "P$24_P$29") (pintype "bidirectional"))
    )
    (net (code "228") (name "unconnected-(U$11-P$25-PadP$30)") (class "Default")
      (node (ref "U$11") (pin "P$30") (pinfunction "P$25_P$30") (pintype "bidirectional"))
    )
    (net (code "229") (name "unconnected-(U$11-PadP$1)") (class "Default")
      (node (ref "U$11") (pin "P$1") (pinfunction "P$1_P$1") (pintype "bidirectional"))
    )
    (net (code "230") (name "unconnected-(U$11-PadP$2)") (class "Default")
      (node (ref "U$11") (pin "P$2") (pinfunction "P$2_P$2") (pintype "bidirectional"))
    )
    (net (code "231") (name "unconnected-(U$11-PadP$3)") (class "Default")
      (node (ref "U$11") (pin "P$3") (pinfunction "P$3_P$3") (pintype "bidirectional"))
    )
    (net (code "232") (name "unconnected-(U$11-PadP$4)") (class "Default")
      (node (ref "U$11") (pin "P$4") (pinfunction "P$4_P$4") (pintype "bidirectional"))
    )
    (net (code "233") (name "unconnected-(U$11-PadP$5)") (class "Default")
      (node (ref "U$11") (pin "P$5") (pinfunction "P$5_P$5") (pintype "bidirectional"))
    )
    (net (code "234") (name "unconnected-(U$11-PadP$6)") (class "Default")
      (node (ref "U$11") (pin "P$6") (pinfunction "P$6_P$6") (pintype "bidirectional"))
    )
    (net (code "235") (name "unconnected-(U$11-PadP$7)") (class "Default")
      (node (ref "U$11") (pin "P$7") (pinfunction "P$7_P$7") (pintype "bidirectional"))
    )
    (net (code "236") (name "unconnected-(U$11-PadP$8)") (class "Default")
      (node (ref "U$11") (pin "P$8") (pinfunction "P$8_P$8") (pintype "bidirectional"))
    )
    (net (code "237") (name "unconnected-(U$11-PadP$9)") (class "Default")
      (node (ref "U$11") (pin "P$9") (pinfunction "P$9_P$9") (pintype "bidirectional"))
    )
    (net (code "238") (name "unconnected-(U$11-PadP$10)") (class "Default")
      (node (ref "U$11") (pin "P$10") (pinfunction "P$10_P$10") (pintype "bidirectional"))
    )
    (net (code "239") (name "unconnected-(U$11-PadP$11)") (class "Default")
      (node (ref "U$11") (pin "P$11") (pinfunction "P$11_P$11") (pintype "bidirectional"))
    )
    (net (code "240") (name "unconnected-(U$11-PadP$12)") (class "Default")
      (node (ref "U$11") (pin "P$12") (pinfunction "P$12_P$12") (pintype "bidirectional"))
    )
    (net (code "241") (name "unconnected-(U$11-PadP$13)") (class "Default")
      (node (ref "U$11") (pin "P$13") (pinfunction "P$13_P$13") (pintype "bidirectional"))
    )
    (net (code "242") (name "unconnected-(U$11-PadP$14)") (class "Default")
      (node (ref "U$11") (pin "P$14") (pinfunction "P$14_P$14") (pintype "bidirectional"))
    )
    (net (code "243") (name "unconnected-(U$11-PadP$15)") (class "Default")
      (node (ref "U$11") (pin "P$15") (pinfunction "P$15_P$15") (pintype "bidirectional"))
    )
    (net (code "244") (name "unconnected-(U$12-P$16-PadP$21)") (class "Default")
      (node (ref "U$12") (pin "P$21") (pinfunction "P$16_P$21") (pintype "bidirectional"))
    )
    (net (code "245") (name "unconnected-(U$12-P$17-PadP$22)") (class "Default")
      (node (ref "U$12") (pin "P$22") (pinfunction "P$17_P$22") (pintype "bidirectional"))
    )
    (net (code "246") (name "unconnected-(U$12-P$18-PadP$23)") (class "Default")
      (node (ref "U$12") (pin "P$23") (pinfunction "P$18_P$23") (pintype "bidirectional"))
    )
    (net (code "247") (name "unconnected-(U$12-P$19-PadP$24)") (class "Default")
      (node (ref "U$12") (pin "P$24") (pinfunction "P$19_P$24") (pintype "bidirectional"))
    )
    (net (code "248") (name "unconnected-(U$12-P$20-PadP$25)") (class "Default")
      (node (ref "U$12") (pin "P$25") (pinfunction "P$20_P$25") (pintype "bidirectional"))
    )
    (net (code "249") (name "unconnected-(U$12-P$21-PadP$26)") (class "Default")
      (node (ref "U$12") (pin "P$26") (pinfunction "P$21_P$26") (pintype "bidirectional"))
    )
    (net (code "250") (name "unconnected-(U$12-P$22-PadP$27)") (class "Default")
      (node (ref "U$12") (pin "P$27") (pinfunction "P$22_P$27") (pintype "bidirectional"))
    )
    (net (code "251") (name "unconnected-(U$12-P$23-PadP$28)") (class "Default")
      (node (ref "U$12") (pin "P$28") (pinfunction "P$23_P$28") (pintype "bidirectional"))
    )
    (net (code "252") (name "unconnected-(U$12-P$24-PadP$29)") (class "Default")
      (node (ref "U$12") (pin "P$29") (pinfunction "P$24_P$29") (pintype "bidirectional"))
    )
    (net (code "253") (name "unconnected-(U$12-P$25-PadP$30)") (class "Default")
      (node (ref "U$12") (pin "P$30") (pinfunction "P$25_P$30") (pintype "bidirectional"))
    )
    (net (code "254") (name "unconnected-(U$12-PadP$1)") (class "Default")
      (node (ref "U$12") (pin "P$1") (pinfunction "P$1_P$1") (pintype "bidirectional"))
    )
    (net (code "255") (name "unconnected-(U$12-PadP$2)") (class "Default")
      (node (ref "U$12") (pin "P$2") (pinfunction "P$2_P$2") (pintype "bidirectional"))
    )
    (net (code "256") (name "unconnected-(U$12-PadP$3)") (class "Default")
      (node (ref "U$12") (pin "P$3") (pinfunction "P$3_P$3") (pintype "bidirectional"))
    )
    (net (code "257") (name "unconnected-(U$12-PadP$4)") (class "Default")
      (node (ref "U$12") (pin "P$4") (pinfunction "P$4_P$4") (pintype "bidirectional"))
    )
    (net (code "258") (name "unconnected-(U$12-PadP$5)") (class "Default")
      (node (ref "U$12") (pin "P$5") (pinfunction "P$5_P$5") (pintype "bidirectional"))
    )
    (net (code "259") (name "unconnected-(U$12-PadP$6)") (class "Default")
      (node (ref "U$12") (pin "P$6") (pinfunction "P$6_P$6") (pintype "bidirectional"))
    )
    (net (code "260") (name "unconnected-(U$12-PadP$7)") (class "Default")
      (node (ref "U$12") (pin "P$7") (pinfunction "P$7_P$7") (pintype "bidirectional"))
    )
    (net (code "261") (name "unconnected-(U$12-PadP$8)") (class "Default")
      (node (ref "U$12") (pin "P$8") (pinfunction "P$8_P$8") (pintype "bidirectional"))
    )
    (net (code "262") (name "unconnected-(U$12-PadP$9)") (class "Default")
      (node (ref "U$12") (pin "P$9") (pinfunction "P$9_P$9") (pintype "bidirectional"))
    )
    (net (code "263") (name "unconnected-(U$12-PadP$10)") (class "Default")
      (node (ref "U$12") (pin "P$10") (pinfunction "P$10_P$10") (pintype "bidirectional"))
    )
    (net (code "264") (name "unconnected-(U$12-PadP$11)") (class "Default")
      (node (ref "U$12") (pin "P$11") (pinfunction "P$11_P$11") (pintype "bidirectional"))
    )
    (net (code "265") (name "unconnected-(U$12-PadP$12)") (class "Default")
      (node (ref "U$12") (pin "P$12") (pinfunction "P$12_P$12") (pintype "bidirectional"))
    )
    (net (code "266") (name "unconnected-(U$12-PadP$13)") (class "Default")
      (node (ref "U$12") (pin "P$13") (pinfunction "P$13_P$13") (pintype "bidirectional"))
    )
    (net (code "267") (name "unconnected-(U$12-PadP$14)") (class "Default")
      (node (ref "U$12") (pin "P$14") (pinfunction "P$14_P$14") (pintype "bidirectional"))
    )
    (net (code "268") (name "unconnected-(U$12-PadP$15)") (class "Default")
      (node (ref "U$12") (pin "P$15") (pinfunction "P$15_P$15") (pintype "bidirectional"))
    )
    (net (code "269") (name "unconnected-(U$13-P$16-PadP$21)") (class "Default")
      (node (ref "U$13") (pin "P$21") (pinfunction "P$16_P$21") (pintype "bidirectional"))
    )
    (net (code "270") (name "unconnected-(U$13-P$17-PadP$22)") (class "Default")
      (node (ref "U$13") (pin "P$22") (pinfunction "P$17_P$22") (pintype "bidirectional"))
    )
    (net (code "271") (name "unconnected-(U$13-P$18-PadP$23)") (class "Default")
      (node (ref "U$13") (pin "P$23") (pinfunction "P$18_P$23") (pintype "bidirectional"))
    )
    (net (code "272") (name "unconnected-(U$13-P$19-PadP$24)") (class "Default")
      (node (ref "U$13") (pin "P$24") (pinfunction "P$19_P$24") (pintype "bidirectional"))
    )
    (net (code "273") (name "unconnected-(U$13-P$20-PadP$25)") (class "Default")
      (node (ref "U$13") (pin "P$25") (pinfunction "P$20_P$25") (pintype "bidirectional"))
    )
    (net (code "274") (name "unconnected-(U$13-P$21-PadP$26)") (class "Default")
      (node (ref "U$13") (pin "P$26") (pinfunction "P$21_P$26") (pintype "bidirectional"))
    )
    (net (code "275") (name "unconnected-(U$13-P$22-PadP$27)") (class "Default")
      (node (ref "U$13") (pin "P$27") (pinfunction "P$22_P$27") (pintype "bidirectional"))
    )
    (net (code "276") (name "unconnected-(U$13-P$23-PadP$28)") (class "Default")
      (node (ref "U$13") (pin "P$28") (pinfunction "P$23_P$28") (pintype "bidirectional"))
    )
    (net (code "277") (name "unconnected-(U$13-P$24-PadP$29)") (class "Default")
      (node (ref "U$13") (pin "P$29") (pinfunction "P$24_P$29") (pintype "bidirectional"))
    )
    (net (code "278") (name "unconnected-(U$13-P$25-PadP$30)") (class "Default")
      (node (ref "U$13") (pin "P$30") (pinfunction "P$25_P$30") (pintype "bidirectional"))
    )
    (net (code "279") (name "unconnected-(U$13-PadP$1)") (class "Default")
      (node (ref "U$13") (pin "P$1") (pinfunction "P$1_P$1") (pintype "bidirectional"))
    )
    (net (code "280") (name "unconnected-(U$13-PadP$2)") (class "Default")
      (node (ref "U$13") (pin "P$2") (pinfunction "P$2_P$2") (pintype "bidirectional"))
    )
    (net (code "281") (name "unconnected-(U$13-PadP$3)") (class "Default")
      (node (ref "U$13") (pin "P$3") (pinfunction "P$3_P$3") (pintype "bidirectional"))
    )
    (net (code "282") (name "unconnected-(U$13-PadP$4)") (class "Default")
      (node (ref "U$13") (pin "P$4") (pinfunction "P$4_P$4") (pintype "bidirectional"))
    )
    (net (code "283") (name "unconnected-(U$13-PadP$5)") (class "Default")
      (node (ref "U$13") (pin "P$5") (pinfunction "P$5_P$5") (pintype "bidirectional"))
    )
    (net (code "284") (name "unconnected-(U$13-PadP$6)") (class "Default")
      (node (ref "U$13") (pin "P$6") (pinfunction "P$6_P$6") (pintype "bidirectional"))
    )
    (net (code "285") (name "unconnected-(U$13-PadP$7)") (class "Default")
      (node (ref "U$13") (pin "P$7") (pinfunction "P$7_P$7") (pintype "bidirectional"))
    )
    (net (code "286") (name "unconnected-(U$13-PadP$8)") (class "Default")
      (node (ref "U$13") (pin "P$8") (pinfunction "P$8_P$8") (pintype "bidirectional"))
    )
    (net (code "287") (name "unconnected-(U$13-PadP$9)") (class "Default")
      (node (ref "U$13") (pin "P$9") (pinfunction "P$9_P$9") (pintype "bidirectional"))
    )
    (net (code "288") (name "unconnected-(U$13-PadP$10)") (class "Default")
      (node (ref "U$13") (pin "P$10") (pinfunction "P$10_P$10") (pintype "bidirectional"))
    )
    (net (code "289") (name "unconnected-(U$13-PadP$11)") (class "Default")
      (node (ref "U$13") (pin "P$11") (pinfunction "P$11_P$11") (pintype "bidirectional"))
    )
    (net (code "290") (name "unconnected-(U$13-PadP$12)") (class "Default")
      (node (ref "U$13") (pin "P$12") (pinfunction "P$12_P$12") (pintype "bidirectional"))
    )
    (net (code "291") (name "unconnected-(U$13-PadP$13)") (class "Default")
      (node (ref "U$13") (pin "P$13") (pinfunction "P$13_P$13") (pintype "bidirectional"))
    )
    (net (code "292") (name "unconnected-(U$13-PadP$14)") (class "Default")
      (node (ref "U$13") (pin "P$14") (pinfunction "P$14_P$14") (pintype "bidirectional"))
    )
    (net (code "293") (name "unconnected-(U$13-PadP$15)") (class "Default")
      (node (ref "U$13") (pin "P$15") (pinfunction "P$15_P$15") (pintype "bidirectional"))
    )
    (net (code "294") (name "unconnected-(U$14-P$16-PadP$21)") (class "Default")
      (node (ref "U$14") (pin "P$21") (pinfunction "P$16_P$21") (pintype "bidirectional"))
    )
    (net (code "295") (name "unconnected-(U$14-P$17-PadP$22)") (class "Default")
      (node (ref "U$14") (pin "P$22") (pinfunction "P$17_P$22") (pintype "bidirectional"))
    )
    (net (code "296") (name "unconnected-(U$14-P$18-PadP$23)") (class "Default")
      (node (ref "U$14") (pin "P$23") (pinfunction "P$18_P$23") (pintype "bidirectional"))
    )
    (net (code "297") (name "unconnected-(U$14-P$19-PadP$24)") (class "Default")
      (node (ref "U$14") (pin "P$24") (pinfunction "P$19_P$24") (pintype "bidirectional"))
    )
    (net (code "298") (name "unconnected-(U$14-P$20-PadP$25)") (class "Default")
      (node (ref "U$14") (pin "P$25") (pinfunction "P$20_P$25") (pintype "bidirectional"))
    )
    (net (code "299") (name "unconnected-(U$14-P$21-PadP$26)") (class "Default")
      (node (ref "U$14") (pin "P$26") (pinfunction "P$21_P$26") (pintype "bidirectional"))
    )
    (net (code "300") (name "unconnected-(U$14-P$22-PadP$27)") (class "Default")
      (node (ref "U$14") (pin "P$27") (pinfunction "P$22_P$27") (pintype "bidirectional"))
    )
    (net (code "301") (name "unconnected-(U$14-P$23-PadP$28)") (class "Default")
      (node (ref "U$14") (pin "P$28") (pinfunction "P$23_P$28") (pintype "bidirectional"))
    )
    (net (code "302") (name "unconnected-(U$14-P$24-PadP$29)") (class "Default")
      (node (ref "U$14") (pin "P$29") (pinfunction "P$24_P$29") (pintype "bidirectional"))
    )
    (net (code "303") (name "unconnected-(U$14-P$25-PadP$30)") (class "Default")
      (node (ref "U$14") (pin "P$30") (pinfunction "P$25_P$30") (pintype "bidirectional"))
    )
    (net (code "304") (name "unconnected-(U$14-PadP$1)") (class "Default")
      (node (ref "U$14") (pin "P$1") (pinfunction "P$1_P$1") (pintype "bidirectional"))
    )
    (net (code "305") (name "unconnected-(U$14-PadP$2)") (class "Default")
      (node (ref "U$14") (pin "P$2") (pinfunction "P$2_P$2") (pintype "bidirectional"))
    )
    (net (code "306") (name "unconnected-(U$14-PadP$3)") (class "Default")
      (node (ref "U$14") (pin "P$3") (pinfunction "P$3_P$3") (pintype "bidirectional"))
    )
    (net (code "307") (name "unconnected-(U$14-PadP$4)") (class "Default")
      (node (ref "U$14") (pin "P$4") (pinfunction "P$4_P$4") (pintype "bidirectional"))
    )
    (net (code "308") (name "unconnected-(U$14-PadP$5)") (class "Default")
      (node (ref "U$14") (pin "P$5") (pinfunction "P$5_P$5") (pintype "bidirectional"))
    )
    (net (code "309") (name "unconnected-(U$14-PadP$6)") (class "Default")
      (node (ref "U$14") (pin "P$6") (pinfunction "P$6_P$6") (pintype "bidirectional"))
    )
    (net (code "310") (name "unconnected-(U$14-PadP$7)") (class "Default")
      (node (ref "U$14") (pin "P$7") (pinfunction "P$7_P$7") (pintype "bidirectional"))
    )
    (net (code "311") (name "unconnected-(U$14-PadP$8)") (class "Default")
      (node (ref "U$14") (pin "P$8") (pinfunction "P$8_P$8") (pintype "bidirectional"))
    )
    (net (code "312") (name "unconnected-(U$14-PadP$9)") (class "Default")
      (node (ref "U$14") (pin "P$9") (pinfunction "P$9_P$9") (pintype "bidirectional"))
    )
    (net (code "313") (name "unconnected-(U$14-PadP$10)") (class "Default")
      (node (ref "U$14") (pin "P$10") (pinfunction "P$10_P$10") (pintype "bidirectional"))
    )
    (net (code "314") (name "unconnected-(U$14-PadP$11)") (class "Default")
      (node (ref "U$14") (pin "P$11") (pinfunction "P$11_P$11") (pintype "bidirectional"))
    )
    (net (code "315") (name "unconnected-(U$14-PadP$12)") (class "Default")
      (node (ref "U$14") (pin "P$12") (pinfunction "P$12_P$12") (pintype "bidirectional"))
    )
    (net (code "316") (name "unconnected-(U$14-PadP$13)") (class "Default")
      (node (ref "U$14") (pin "P$13") (pinfunction "P$13_P$13") (pintype "bidirectional"))
    )
    (net (code "317") (name "unconnected-(U$14-PadP$14)") (class "Default")
      (node (ref "U$14") (pin "P$14") (pinfunction "P$14_P$14") (pintype "bidirectional"))
    )
    (net (code "318") (name "unconnected-(U$14-PadP$15)") (class "Default")
      (node (ref "U$14") (pin "P$15") (pinfunction "P$15_P$15") (pintype "bidirectional"))
    )
  )
)
